# 15-FPGA-01b.net
KiCad netlist of a schematic drawn in Altium Designer
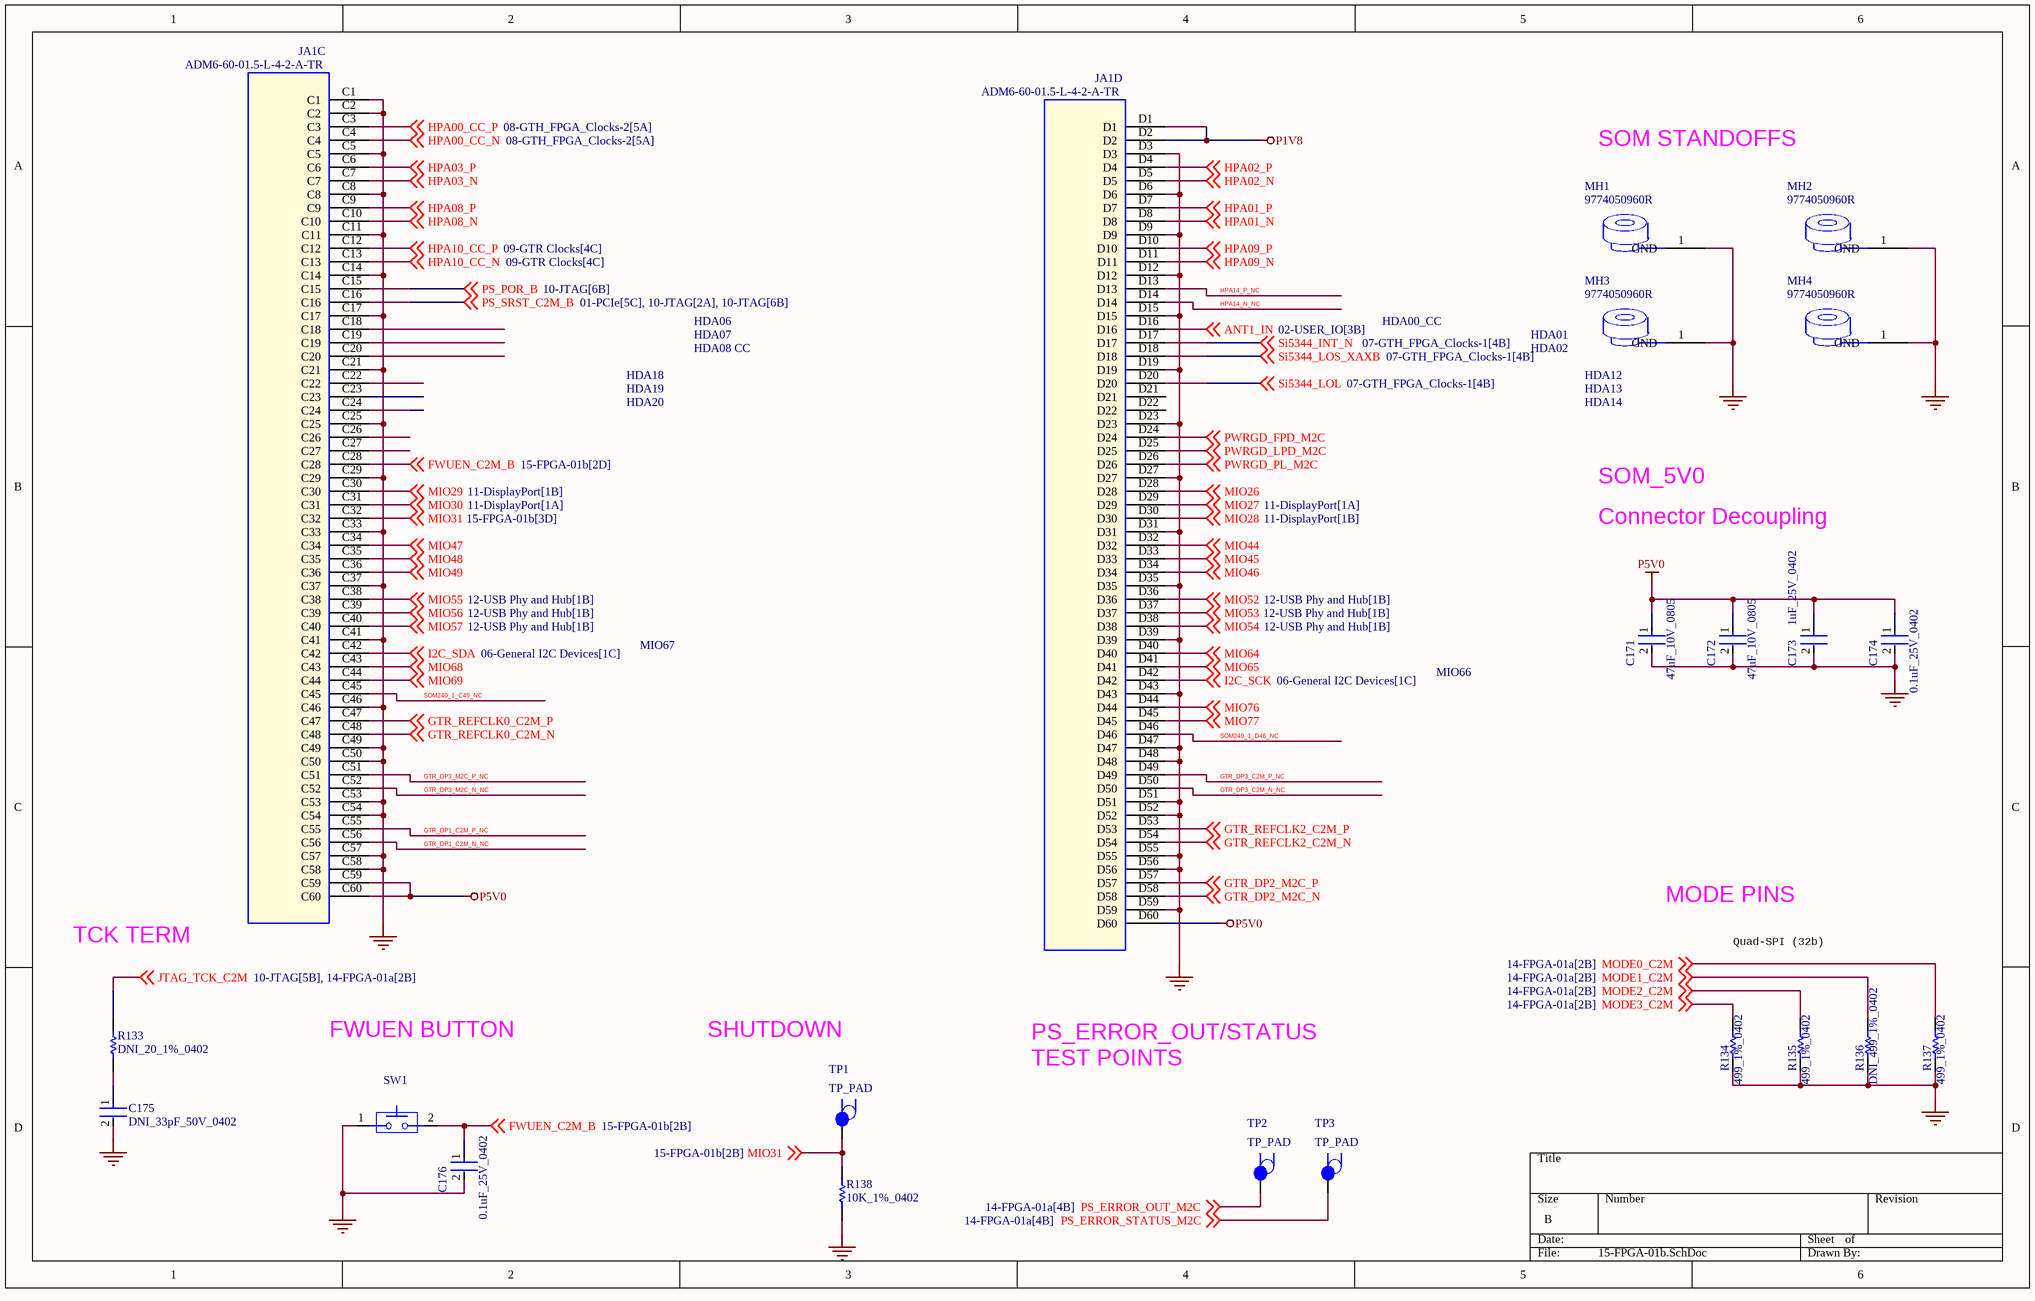
[diagram p0: 15-FPGA-01b.SchDoc]

(export (version "E")
  (design (tool "Eeschema 10.0.6"))
  (components
    (comp (ref "C171")
      (value "47uF_10V_0805")
      (footprint "FP-GRM21B-0_2-e0_2_0_7-IPC_A")
      (description "Chip Multilayer Ceramic Capacitors for General Purpose, 0805, 47uF, X5R, 15%, 20%, 10V")
      (fields (field (name "TOLERANCE") "20%") (field (name "VOLTAGE") "10V"))
      (libsource (lib "Altium Content Vault") (part "b4654b650e69147ec39a6b967a45e02"))
    )
    (comp (ref "C172")
      (value "47uF_10V_0805")
      (footprint "FP-GRM21B-0_2-e0_2_0_7-IPC_A")
      (description "Chip Multilayer Ceramic Capacitors for General Purpose, 0805, 47uF, X5R, 15%, 20%, 10V")
      (fields (field (name "TOLERANCE") "20%") (field (name "VOLTAGE") "10V"))
      (libsource (lib "Altium Content Vault") (part "b4654b650e69147ec39a6b967a45e02"))
    )
    (comp (ref "C173")
      (value "1uF_25V_0402")
      (footprint "FP-CL542-IPC_C")
      (description "Cap Ceramic 1uF 25V X5R ±10% SMD 0402 +85°C Paper T/R")
      (fields (field (name "TOLERANCE") "10%"))
      (libsource (lib "Altium Content Vault") (part "b4654b650e69147ec39a6b967a45e02"))
    )
    (comp (ref "C174")
      (value "0.1uF_25V_0402")
      (footprint "FP-0402-L_1_0_0_05-W_0_5-IPC_B")
      (description "None")
      (fields (field (name "TOLERANCE") "10%") (field (name "VOLTAGE") "25V"))
      (libsource (lib "Altium Content Vault") (part "b4654b650e69147ec39a6b967a45e02"))
    )
    (comp (ref "C175")
      (value "DNI_33pF_50V_0402")
      (footprint "FP-C1005-050-0_05-IPC_A")
      (description "Multilayer Ceramic Capacitors 33pF ±1% 50V C0G SMD 0402")
      (fields (field (name "TOLERANCE") "1%"))
      (libsource (lib "Altium Content Vault") (part "b4654b650e69147ec39a6b967a45e02"))
    )
    (comp (ref "C176")
      (value "0.1uF_25V_0402")
      (footprint "FP-0402-L_1_0_0_05-W_0_5-IPC_B")
      (description "None")
      (fields (field (name "TOLERANCE") "10%") (field (name "VOLTAGE") "25V"))
      (libsource (lib "Altium Content Vault") (part "b4654b650e69147ec39a6b967a45e02"))
    )
    (comp (ref "JA1")
      (value "ADM6-60-01.5-L-4-2-A-TR")
      (footprint "CON_SAMTEC_ADM6_60_4")
      (description "Conn Rcpt Male Vert 240 Pos 4x60 0.635mm P Black SMT")
      (fields (field (name "MANUFACTURER") "Samtec Inc.") (field (name "AGILE PART NUMBER") "CON-00383-01"))
      (libsource (lib "*") (part "SAMTEC-ADx6-60X4"))
    )
    (comp (ref "MH1")
      (value "9774050960R")
      (footprint "CON_WE_WA-SMST_6MM")
      (description "Standoff Female 3.3mm ID 5mm L 7.4mm OD SMT/TH Steel")
      (fields
        (field (name "MANUFACTURER") "Würth Elektronik")
        (field (name "AGILE PART NUMBER") "MEC-00173-01")
      )
      (libsource (lib "*") (part "MECH_SPACER"))
    )
    (comp (ref "MH2")
      (value "9774050960R")
      (footprint "CON_WE_WA-SMST_6MM")
      (description "Standoff Female 3.3mm ID 5mm L 7.4mm OD SMT/TH Steel")
      (fields
        (field (name "MANUFACTURER") "Würth Elektronik")
        (field (name "AGILE PART NUMBER") "MEC-00173-01")
      )
      (libsource (lib "*") (part "MECH_SPACER"))
    )
    (comp (ref "MH3")
      (value "9774050960R")
      (footprint "CON_WE_WA-SMST_6MM")
      (description "Standoff Female 3.3mm ID 5mm L 7.4mm OD SMT/TH Steel")
      (fields
        (field (name "MANUFACTURER") "Würth Elektronik")
        (field (name "AGILE PART NUMBER") "MEC-00173-01")
      )
      (libsource (lib "*") (part "MECH_SPACER"))
    )
    (comp (ref "MH4")
      (value "9774050960R")
      (footprint "CON_WE_WA-SMST_6MM")
      (description "Standoff Female 3.3mm ID 5mm L 7.4mm OD SMT/TH Steel")
      (fields
        (field (name "MANUFACTURER") "Würth Elektronik")
        (field (name "AGILE PART NUMBER") "MEC-00173-01")
      )
      (libsource (lib "*") (part "MECH_SPACER"))
    )
    (comp (ref "R133")
      (value "DNI_20_1%_0402")
      (footprint "RESC1005X40X25NL10T10")
      (fields
        (field (name "MANUFACTURER") "TE Connectivity / AMP")
        (field (name "PART NUMBER") "CRG0402F20R")
      )
      (libsource (lib "Altium Content Vault") (part "RES"))
    )
    (comp (ref "R134")
      (value "499_1%_0402")
      (footprint "RESC1005X40X25LL05T05")
      (fields (field (name "MANUFACTURER") "Vishay Dale") (field (name "PART NUMBER") "CRCW0402499RFKTD"))
      (libsource (lib "Altium Content Vault") (part "RES"))
    )
    (comp (ref "R135")
      (value "499_1%_0402")
      (footprint "RESC1005X40X25LL05T05")
      (fields (field (name "MANUFACTURER") "Vishay Dale") (field (name "PART NUMBER") "CRCW0402499RFKTD"))
      (libsource (lib "Altium Content Vault") (part "RES"))
    )
    (comp (ref "R136")
      (value "DNI_499_1%_0402")
      (footprint "RESC1005X40X25LL05T05")
      (fields (field (name "MANUFACTURER") "Vishay Dale") (field (name "PART NUMBER") "CRCW0402499RFKTD"))
      (libsource (lib "Altium Content Vault") (part "RES"))
    )
    (comp (ref "R137")
      (value "499_1%_0402")
      (footprint "RESC1005X40X25LL05T05")
      (fields (field (name "MANUFACTURER") "Vishay Dale") (field (name "PART NUMBER") "CRCW0402499RFKTD"))
      (libsource (lib "Altium Content Vault") (part "RES"))
    )
    (comp (ref "R138")
      (value "10K_1%_0402")
      (footprint "RESC1005X40X25ML05T05")
      (fields (field (name "PART NUMBER") "ERJ-2GEJ103X") (field (name "MANUFACTURER") "Panasonic"))
      (libsource (lib "Altium Content Vault") (part "RES"))
    )
    (comp (ref "SW1")
      (value "B3U-1000P")
      (footprint "SW_OMRON_2P")
      (description "Switch SPST-NO Mom 50mA 12V 1.6mm H 1.5Nw SMT IP40")
      (fields (field (name "MANUFACTURER") "OMRON") (field (name "AGILE PART NUMBER") "SWH-00003-01"))
      (libsource (lib "*") (part "BTN_MOMENT"))
    )
    (comp (ref "TP1")
      (value "TP_PAD")
      (footprint "TP_PAD")
      (description "TEST POINT 24mil SM pad")
      (fields (field (name "MANF") "DNP") (field (name "OWNER") "3709"))
      (libsource (lib "*") (part "TP"))
    )
    (comp (ref "TP2")
      (value "TP_PAD")
      (footprint "TP_PAD")
      (description "TEST POINT 24mil SM pad")
      (fields (field (name "MANF") "DNP") (field (name "OWNER") "3709"))
      (libsource (lib "*") (part "TP"))
    )
    (comp (ref "TP3")
      (value "TP_PAD")
      (footprint "TP_PAD")
      (description "TEST POINT 24mil SM pad")
      (fields (field (name "MANF") "DNP") (field (name "OWNER") "3709"))
      (libsource (lib "*") (part "TP"))
    )
  )
  (nets
    (net (code "1") (name "/GTR_DP1_C2M_N_NC") (class "Default")
      (node (ref "JA1") (pin "C56") (pinfunction "C56_C56") (pintype "passive"))
    )
    (net (code "2") (name "/GTR_DP1_C2M_P_NC") (class "Default")
      (node (ref "JA1") (pin "C55") (pinfunction "C55_C55") (pintype "passive"))
    )
    (net (code "3") (name "/GTR_DP3_C2M_N_NC") (class "Default")
      (node (ref "JA1") (pin "D50") (pinfunction "D50_D50") (pintype "passive"))
    )
    (net (code "4") (name "/GTR_DP3_C2M_P_NC") (class "Default")
      (node (ref "JA1") (pin "D49") (pinfunction "D49_D49") (pintype "passive"))
    )
    (net (code "5") (name "/GTR_DP3_M2C_N_NC") (class "Default")
      (node (ref "JA1") (pin "C52") (pinfunction "C52_C52") (pintype "passive"))
    )
    (net (code "6") (name "/GTR_DP3_M2C_P_NC") (class "Default")
      (node (ref "JA1") (pin "C51") (pinfunction "C51_C51") (pintype "passive"))
    )
    (net (code "7") (name "/HPA14_N_NC") (class "Default")
      (node (ref "JA1") (pin "D14") (pinfunction "D14_D14") (pintype "passive"))
    )
    (net (code "8") (name "/HPA14_P_NC") (class "Default")
      (node (ref "JA1") (pin "D13") (pinfunction "D13_D13") (pintype "passive"))
    )
    (net (code "9") (name "/SOM240_1_C45_NC") (class "Default")
      (node (ref "JA1") (pin "C45") (pinfunction "C45_C45") (pintype "passive"))
    )
    (net (code "10") (name "/SOM240_1_D46_NC") (class "Default")
      (node (ref "JA1") (pin "D46") (pinfunction "D46_D46") (pintype "passive"))
    )
    (net (code "11") (name "ANT1_IN") (class "Default")
      (node (ref "JA1") (pin "D16") (pinfunction "D16_D16") (pintype "passive"))
    )
    (net (code "12") (name "FWUEN_C2M_B") (class "Default")
      (node (ref "C176") (pin "1") (pinfunction "1_1") (pintype "passive"))
      (node (ref "JA1") (pin "C28") (pinfunction "C28_C28") (pintype "passive"))
      (node (ref "SW1") (pin "2") (pinfunction "SW2_2") (pintype "passive"))
    )
    (net (code "13") (name "GND") (class "Default")
      (node (ref "C171") (pin "2") (pinfunction "2_2") (pintype "passive"))
      (node (ref "C172") (pin "2") (pinfunction "2_2") (pintype "passive"))
      (node (ref "C173") (pin "2") (pinfunction "2_2") (pintype "passive"))
      (node (ref "C174") (pin "2") (pinfunction "2_2") (pintype "passive"))
      (node (ref "C175") (pin "2") (pinfunction "2_2") (pintype "passive"))
      (node (ref "C176") (pin "2") (pinfunction "2_2") (pintype "passive"))
      (node (ref "JA1") (pin "C1") (pinfunction "C1_C1") (pintype "passive"))
      (node (ref "JA1") (pin "C11") (pinfunction "C11_C11") (pintype "passive"))
      (node (ref "JA1") (pin "C14") (pinfunction "C14_C14") (pintype "passive"))
      (node (ref "JA1") (pin "C17") (pinfunction "C17_C17") (pintype "passive"))
      (node (ref "JA1") (pin "C2") (pinfunction "C2_C2") (pintype "passive"))
      (node (ref "JA1") (pin "C21") (pinfunction "C21_C21") (pintype "passive"))
      (node (ref "JA1") (pin "C25") (pinfunction "C25_C25") (pintype "passive"))
      (node (ref "JA1") (pin "C29") (pinfunction "C29_C29") (pintype "passive"))
      (node (ref "JA1") (pin "C33") (pinfunction "C33_C33") (pintype "passive"))
      (node (ref "JA1") (pin "C37") (pinfunction "C37_C37") (pintype "passive"))
      (node (ref "JA1") (pin "C41") (pinfunction "C41_C41") (pintype "passive"))
      (node (ref "JA1") (pin "C46") (pinfunction "C46_C46") (pintype "passive"))
      (node (ref "JA1") (pin "C49") (pinfunction "C49_C49") (pintype "passive"))
      (node (ref "JA1") (pin "C5") (pinfunction "C5_C5") (pintype "passive"))
      (node (ref "JA1") (pin "C50") (pinfunction "C50_C50") (pintype "passive"))
      (node (ref "JA1") (pin "C53") (pinfunction "C53_C53") (pintype "passive"))
      (node (ref "JA1") (pin "C54") (pinfunction "C54_C54") (pintype "passive"))
      (node (ref "JA1") (pin "C57") (pinfunction "C57_C57") (pintype "passive"))
      (node (ref "JA1") (pin "C58") (pinfunction "C58_C58") (pintype "passive"))
      (node (ref "JA1") (pin "C8") (pinfunction "C8_C8") (pintype "passive"))
      (node (ref "JA1") (pin "D12") (pinfunction "D12_D12") (pintype "passive"))
      (node (ref "JA1") (pin "D15") (pinfunction "D15_D15") (pintype "passive"))
      (node (ref "JA1") (pin "D19") (pinfunction "D19_D19") (pintype "passive"))
      (node (ref "JA1") (pin "D23") (pinfunction "D23_D23") (pintype "passive"))
      (node (ref "JA1") (pin "D27") (pinfunction "D27_D27") (pintype "passive"))
      (node (ref "JA1") (pin "D3") (pinfunction "D3_D3") (pintype "passive"))
      (node (ref "JA1") (pin "D31") (pinfunction "D31_D31") (pintype "passive"))
      (node (ref "JA1") (pin "D35") (pinfunction "D35_D35") (pintype "passive"))
      (node (ref "JA1") (pin "D39") (pinfunction "D39_D39") (pintype "passive"))
      (node (ref "JA1") (pin "D43") (pinfunction "D43_D43") (pintype "passive"))
      (node (ref "JA1") (pin "D47") (pinfunction "D47_D47") (pintype "passive"))
      (node (ref "JA1") (pin "D48") (pinfunction "D48_D48") (pintype "passive"))
      (node (ref "JA1") (pin "D51") (pinfunction "D51_D51") (pintype "passive"))
      (node (ref "JA1") (pin "D52") (pinfunction "D52_D52") (pintype "passive"))
      (node (ref "JA1") (pin "D55") (pinfunction "D55_D55") (pintype "passive"))
      (node (ref "JA1") (pin "D56") (pinfunction "D56_D56") (pintype "passive"))
      (node (ref "JA1") (pin "D59") (pinfunction "D59_D59") (pintype "passive"))
      (node (ref "JA1") (pin "D6") (pinfunction "D6_D6") (pintype "passive"))
      (node (ref "JA1") (pin "D9") (pinfunction "D9_D9") (pintype "passive"))
      (node (ref "MH1") (pin "1") (pinfunction "GND_1") (pintype "power_in"))
      (node (ref "MH2") (pin "1") (pinfunction "GND_1") (pintype "power_in"))
      (node (ref "MH3") (pin "1") (pinfunction "GND_1") (pintype "power_in"))
      (node (ref "MH4") (pin "1") (pinfunction "GND_1") (pintype "power_in"))
      (node (ref "R134") (pin "1") (pinfunction "1_1") (pintype "passive"))
      (node (ref "R135") (pin "1") (pinfunction "1_1") (pintype "passive"))
      (node (ref "R136") (pin "1") (pinfunction "1_1") (pintype "passive"))
      (node (ref "R137") (pin "1") (pinfunction "1_1") (pintype "passive"))
      (node (ref "R138") (pin "1") (pinfunction "1_1") (pintype "passive"))
      (node (ref "SW1") (pin "1") (pinfunction "SW1_1") (pintype "passive"))
    )
    (net (code "14") (name "GTR_DP2_M2C_N") (class "Default")
      (node (ref "JA1") (pin "D58") (pinfunction "D58_D58") (pintype "passive"))
    )
    (net (code "15") (name "GTR_DP2_M2C_P") (class "Default")
      (node (ref "JA1") (pin "D57") (pinfunction "D57_D57") (pintype "passive"))
    )
    (net (code "16") (name "GTR_REFCLK0_C2M_N") (class "Default")
      (node (ref "JA1") (pin "C48") (pinfunction "C48_C48") (pintype "passive"))
    )
    (net (code "17") (name "GTR_REFCLK0_C2M_P") (class "Default")
      (node (ref "JA1") (pin "C47") (pinfunction "C47_C47") (pintype "passive"))
    )
    (net (code "18") (name "GTR_REFCLK2_C2M_N") (class "Default")
      (node (ref "JA1") (pin "D54") (pinfunction "D54_D54") (pintype "passive"))
    )
    (net (code "19") (name "GTR_REFCLK2_C2M_P") (class "Default")
      (node (ref "JA1") (pin "D53") (pinfunction "D53_D53") (pintype "passive"))
    )
    (net (code "20") (name "HPA00_CC_N") (class "Default")
      (node (ref "JA1") (pin "C4") (pinfunction "C4_C4") (pintype "passive"))
    )
    (net (code "21") (name "HPA00_CC_P") (class "Default")
      (node (ref "JA1") (pin "C3") (pinfunction "C3_C3") (pintype "passive"))
    )
    (net (code "22") (name "HPA01_N") (class "Default")
      (node (ref "JA1") (pin "D8") (pinfunction "D8_D8") (pintype "passive"))
    )
    (net (code "23") (name "HPA01_P") (class "Default")
      (node (ref "JA1") (pin "D7") (pinfunction "D7_D7") (pintype "passive"))
    )
    (net (code "24") (name "HPA02_N") (class "Default")
      (node (ref "JA1") (pin "D5") (pinfunction "D5_D5") (pintype "passive"))
    )
    (net (code "25") (name "HPA02_P") (class "Default")
      (node (ref "JA1") (pin "D4") (pinfunction "D4_D4") (pintype "passive"))
    )
    (net (code "26") (name "HPA03_N") (class "Default")
      (node (ref "JA1") (pin "C7") (pinfunction "C7_C7") (pintype "passive"))
    )
    (net (code "27") (name "HPA03_P") (class "Default")
      (node (ref "JA1") (pin "C6") (pinfunction "C6_C6") (pintype "passive"))
    )
    (net (code "28") (name "HPA08_N") (class "Default")
      (node (ref "JA1") (pin "C10") (pinfunction "C10_C10") (pintype "passive"))
    )
    (net (code "29") (name "HPA08_P") (class "Default")
      (node (ref "JA1") (pin "C9") (pinfunction "C9_C9") (pintype "passive"))
    )
    (net (code "30") (name "HPA09_N") (class "Default")
      (node (ref "JA1") (pin "D11") (pinfunction "D11_D11") (pintype "passive"))
    )
    (net (code "31") (name "HPA09_P") (class "Default")
      (node (ref "JA1") (pin "D10") (pinfunction "D10_D10") (pintype "passive"))
    )
    (net (code "32") (name "HPA10_CC_N") (class "Default")
      (node (ref "JA1") (pin "C13") (pinfunction "C13_C13") (pintype "passive"))
    )
    (net (code "33") (name "HPA10_CC_P") (class "Default")
      (node (ref "JA1") (pin "C12") (pinfunction "C12_C12") (pintype "passive"))
    )
    (net (code "34") (name "I2C_SCK") (class "Default")
      (node (ref "JA1") (pin "D42") (pinfunction "D42_D42") (pintype "passive"))
    )
    (net (code "35") (name "I2C_SDA") (class "Default")
      (node (ref "JA1") (pin "C42") (pinfunction "C42_C42") (pintype "passive"))
    )
    (net (code "36") (name "JTAG_TCK_C2M") (class "Default")
      (node (ref "R133") (pin "2") (pinfunction "2_2") (pintype "passive"))
    )
    (net (code "37") (name "MIO26") (class "Default")
      (node (ref "JA1") (pin "D28") (pinfunction "D28_D28") (pintype "passive"))
    )
    (net (code "38") (name "MIO27") (class "Default")
      (node (ref "JA1") (pin "D29") (pinfunction "D29_D29") (pintype "passive"))
    )
    (net (code "39") (name "MIO28") (class "Default")
      (node (ref "JA1") (pin "D30") (pinfunction "D30_D30") (pintype "passive"))
    )
    (net (code "40") (name "MIO29") (class "Default")
      (node (ref "JA1") (pin "C30") (pinfunction "C30_C30") (pintype "passive"))
    )
    (net (code "41") (name "MIO30") (class "Default")
      (node (ref "JA1") (pin "C31") (pinfunction "C31_C31") (pintype "passive"))
    )
    (net (code "42") (name "MIO31") (class "Default")
      (node (ref "JA1") (pin "C32") (pinfunction "C32_C32") (pintype "passive"))
      (node (ref "R138") (pin "2") (pinfunction "2_2") (pintype "passive"))
      (node (ref "TP1") (pin "1") (pinfunction "TP_1") (pintype "passive"))
    )
    (net (code "43") (name "MIO44") (class "Default")
      (node (ref "JA1") (pin "D32") (pinfunction "D32_D32") (pintype "passive"))
    )
    (net (code "44") (name "MIO45") (class "Default")
      (node (ref "JA1") (pin "D33") (pinfunction "D33_D33") (pintype "passive"))
    )
    (net (code "45") (name "MIO46") (class "Default")
      (node (ref "JA1") (pin "D34") (pinfunction "D34_D34") (pintype "passive"))
    )
    (net (code "46") (name "MIO47") (class "Default")
      (node (ref "JA1") (pin "C34") (pinfunction "C34_C34") (pintype "passive"))
    )
    (net (code "47") (name "MIO48") (class "Default")
      (node (ref "JA1") (pin "C35") (pinfunction "C35_C35") (pintype "passive"))
    )
    (net (code "48") (name "MIO49") (class "Default")
      (node (ref "JA1") (pin "C36") (pinfunction "C36_C36") (pintype "passive"))
    )
    (net (code "49") (name "MIO52") (class "Default")
      (node (ref "JA1") (pin "D36") (pinfunction "D36_D36") (pintype "passive"))
    )
    (net (code "50") (name "MIO53") (class "Default")
      (node (ref "JA1") (pin "D37") (pinfunction "D37_D37") (pintype "passive"))
    )
    (net (code "51") (name "MIO54") (class "Default")
      (node (ref "JA1") (pin "D38") (pinfunction "D38_D38") (pintype "passive"))
    )
    (net (code "52") (name "MIO55") (class "Default")
      (node (ref "JA1") (pin "C38") (pinfunction "C38_C38") (pintype "passive"))
    )
    (net (code "53") (name "MIO56") (class "Default")
      (node (ref "JA1") (pin "C39") (pinfunction "C39_C39") (pintype "passive"))
    )
    (net (code "54") (name "MIO57") (class "Default")
      (node (ref "JA1") (pin "C40") (pinfunction "C40_C40") (pintype "passive"))
    )
    (net (code "55") (name "MIO64") (class "Default")
      (node (ref "JA1") (pin "D40") (pinfunction "D40_D40") (pintype "passive"))
    )
    (net (code "56") (name "MIO65") (class "Default")
      (node (ref "JA1") (pin "D41") (pinfunction "D41_D41") (pintype "passive"))
    )
    (net (code "57") (name "MIO68") (class "Default")
      (node (ref "JA1") (pin "C43") (pinfunction "C43_C43") (pintype "passive"))
    )
    (net (code "58") (name "MIO69") (class "Default")
      (node (ref "JA1") (pin "C44") (pinfunction "C44_C44") (pintype "passive"))
    )
    (net (code "59") (name "MIO76") (class "Default")
      (node (ref "JA1") (pin "D44") (pinfunction "D44_D44") (pintype "passive"))
    )
    (net (code "60") (name "MIO77") (class "Default")
      (node (ref "JA1") (pin "D45") (pinfunction "D45_D45") (pintype "passive"))
    )
    (net (code "61") (name "MODE0_C2M") (class "Default")
      (node (ref "R137") (pin "2") (pinfunction "2_2") (pintype "passive"))
    )
    (net (code "62") (name "MODE1_C2M") (class "Default")
      (node (ref "R136") (pin "2") (pinfunction "2_2") (pintype "passive"))
    )
    (net (code "63") (name "MODE2_C2M") (class "Default")
      (node (ref "R135") (pin "2") (pinfunction "2_2") (pintype "passive"))
    )
    (net (code "64") (name "MODE3_C2M") (class "Default")
      (node (ref "R134") (pin "2") (pinfunction "2_2") (pintype "passive"))
    )
    (net (code "65") (name "Net-(C175-Pad1)") (class "Default")
      (node (ref "C175") (pin "1") (pinfunction "1_1") (pintype "passive"))
      (node (ref "R133") (pin "1") (pinfunction "1_1") (pintype "passive"))
    )
    (net (code "66") (name "P1V8") (class "Default")
      (node (ref "JA1") (pin "D1") (pinfunction "D1_D1") (pintype "passive"))
      (node (ref "JA1") (pin "D2") (pinfunction "D2_D2") (pintype "passive"))
    )
    (net (code "67") (name "P5V0") (class "Default")
      (node (ref "C171") (pin "1") (pinfunction "1_1") (pintype "passive"))
      (node (ref "C172") (pin "1") (pinfunction "1_1") (pintype "passive"))
      (node (ref "C173") (pin "1") (pinfunction "1_1") (pintype "passive"))
      (node (ref "C174") (pin "1") (pinfunction "1_1") (pintype "passive"))
      (node (ref "JA1") (pin "C59") (pinfunction "C59_C59") (pintype "passive"))
      (node (ref "JA1") (pin "C60") (pinfunction "C60_C60") (pintype "passive"))
      (node (ref "JA1") (pin "D60") (pinfunction "D60_D60") (pintype "passive"))
    )
    (net (code "68") (name "PS_ERROR_OUT_M2C") (class "Default")
      (node (ref "TP2") (pin "1") (pinfunction "TP_1") (pintype "passive"))
    )
    (net (code "69") (name "PS_ERROR_STATUS_M2C") (class "Default")
      (node (ref "TP3") (pin "1") (pinfunction "TP_1") (pintype "passive"))
    )
    (net (code "70") (name "PS_POR_B") (class "Default")
      (node (ref "JA1") (pin "C15") (pinfunction "C15_C15") (pintype "passive"))
    )
    (net (code "71") (name "PS_SRST_C2M_B") (class "Default")
      (node (ref "JA1") (pin "C16") (pinfunction "C16_C16") (pintype "passive"))
    )
    (net (code "72") (name "PWRGD_FPD_M2C") (class "Default")
      (node (ref "JA1") (pin "D24") (pinfunction "D24_D24") (pintype "passive"))
    )
    (net (code "73") (name "PWRGD_LPD_M2C") (class "Default")
      (node (ref "JA1") (pin "D25") (pinfunction "D25_D25") (pintype "passive"))
    )
    (net (code "74") (name "PWRGD_PL_M2C") (class "Default")
      (node (ref "JA1") (pin "D26") (pinfunction "D26_D26") (pintype "passive"))
    )
    (net (code "75") (name "Si5344_INT_N") (class "Default")
      (node (ref "JA1") (pin "D17") (pinfunction "D17_D17") (pintype "passive"))
    )
    (net (code "76") (name "Si5344_LOL") (class "Default")
      (node (ref "JA1") (pin "D20") (pinfunction "D20_D20") (pintype "passive"))
    )
    (net (code "77") (name "Si5344_LOS_XAXB") (class "Default")
      (node (ref "JA1") (pin "D18") (pinfunction "D18_D18") (pintype "passive"))
    )
    (net (code "78") (name "unconnected-(JA1-PadC18)") (class "Default")
      (node (ref "JA1") (pin "C18") (pinfunction "C18_C18") (pintype "passive"))
    )
    (net (code "79") (name "unconnected-(JA1-PadC19)") (class "Default")
      (node (ref "JA1") (pin "C19") (pinfunction "C19_C19") (pintype "passive"))
    )
    (net (code "80") (name "unconnected-(JA1-PadC20)") (class "Default")
      (node (ref "JA1") (pin "C20") (pinfunction "C20_C20") (pintype "passive"))
    )
    (net (code "81") (name "unconnected-(JA1-PadC22)") (class "Default")
      (node (ref "JA1") (pin "C22") (pinfunction "C22_C22") (pintype "passive"))
    )
    (net (code "82") (name "unconnected-(JA1-PadC23)") (class "Default")
      (node (ref "JA1") (pin "C23") (pinfunction "C23_C23") (pintype "passive"))
    )
    (net (code "83") (name "unconnected-(JA1-PadC24)") (class "Default")
      (node (ref "JA1") (pin "C24") (pinfunction "C24_C24") (pintype "passive"))
    )
    (net (code "84") (name "unconnected-(JA1-PadC26)") (class "Default")
      (node (ref "JA1") (pin "C26") (pinfunction "C26_C26") (pintype "passive"))
    )
    (net (code "85") (name "unconnected-(JA1-PadC27)") (class "Default")
      (node (ref "JA1") (pin "C27") (pinfunction "C27_C27") (pintype "passive"))
    )
    (net (code "86") (name "unconnected-(JA1-PadD21)") (class "Default")
      (node (ref "JA1") (pin "D21") (pinfunction "D21_D21") (pintype "passive"))
    )
    (net (code "87") (name "unconnected-(JA1-PadD22)") (class "Default")
      (node (ref "JA1") (pin "D22") (pinfunction "D22_D22") (pintype "passive"))
    )
  )
)
